# test1.net
KiCad netlist of a schematic drawn in Altium Designer
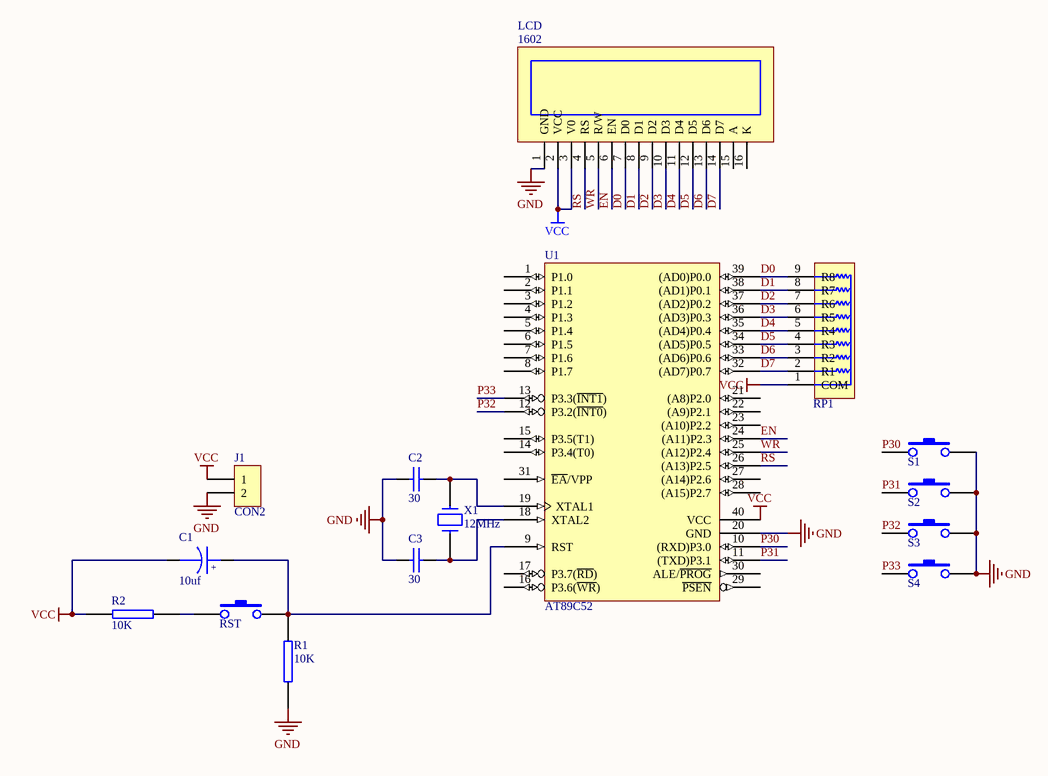
[diagram p0: test1.SchDoc]

(export (version "E")
  (design (tool "Eeschema 10.0.6"))
  (components
    (comp (ref "C1")
      (value "10uf")
      (footprint "C_SMT-5*5")
      (description "Capacitor")
      (libsource (lib "xinweidz") (part "电解电容"))
    )
    (comp (ref "C2")
      (value "30")
      (footprint "C0805")
      (description "Capacitor")
      (libsource (lib "*") (part "CAP"))
    )
    (comp (ref "C3")
      (value "30")
      (footprint "C0805")
      (description "Capacitor")
      (libsource (lib "*") (part "CAP"))
    )
    (comp (ref "J1")
      (value "CON2")
      (footprint "TC2")
      (description "Connector")
      (libsource (lib "51单片机最小系统.PcbDoc") (part "CON2"))
    )
    (comp (ref "LCD") (value "1602") (footprint "LCD1602") (libsource (lib "*") (part "LCM1602")))
    (comp (ref "R1") (value "10K") (footprint "C0805") (libsource (lib "*") (part "RES2")))
    (comp (ref "R2") (value "10K") (footprint "C0805") (libsource (lib "*") (part "RES2")))
    (comp (ref "RP1") (value "103") (footprint "R-9PIN") (libsource (lib "*") (part "RP8")))
    (comp (ref "RST")
      (value "SW-PB")
      (footprint "ANJIAN")
      (libsource (lib "51单片机最小系统.PcbDoc") (part "SW-PB"))
    )
    (comp (ref "S1") (value "SW-PB") (footprint "ANJIAN") (libsource (lib "51单片机最小系统.PcbDoc") (part "SW-PB")))
    (comp (ref "S2") (value "SW-PB") (footprint "ANJIAN") (libsource (lib "51单片机最小系统.PcbDoc") (part "SW-PB")))
    (comp (ref "S3") (value "SW-PB") (footprint "ANJIAN") (libsource (lib "51单片机最小系统.PcbDoc") (part "SW-PB")))
    (comp (ref "S4") (value "SW-PB") (footprint "ANJIAN") (libsource (lib "51单片机最小系统.PcbDoc") (part "SW-PB")))
    (comp (ref "U1")
      (value "AT89C52")
      (footprint "JINSUOZUO")
      (description "8-Bit Microcontroller with 4K Flash ROM")
      (libsource (lib "51单片机最小系统.PcbDoc") (part "AT89C51"))
    )
    (comp (ref "X1")
      (value "12MHz")
      (footprint "XTAL1")
      (description "Crystal")
      (libsource (lib "*") (part "CRYSTAL"))
    )
  )
  (nets
    (net (code "1") (name "/D0") (class "Default")
      (node (ref "LCD") (pin "7") (pinfunction "D0_7") (pintype "passive"))
      (node (ref "RP1") (pin "9") (pinfunction "R8_9") (pintype "passive"))
      (node (ref "U1") (pin "39") (pinfunction "(AD0)P0.0_39") (pintype "bidirectional"))
    )
    (net (code "2") (name "/D1") (class "Default")
      (node (ref "LCD") (pin "8") (pinfunction "D1_8") (pintype "passive"))
      (node (ref "RP1") (pin "8") (pinfunction "R7_8") (pintype "passive"))
      (node (ref "U1") (pin "38") (pinfunction "(AD1)P0.1_38") (pintype "bidirectional"))
    )
    (net (code "3") (name "/D2") (class "Default")
      (node (ref "LCD") (pin "9") (pinfunction "D2_9") (pintype "passive"))
      (node (ref "RP1") (pin "7") (pinfunction "R6_7") (pintype "passive"))
      (node (ref "U1") (pin "37") (pinfunction "(AD2)P0.2_37") (pintype "bidirectional"))
    )
    (net (code "4") (name "/D3") (class "Default")
      (node (ref "LCD") (pin "10") (pinfunction "D3_10") (pintype "passive"))
      (node (ref "RP1") (pin "6") (pinfunction "R5_6") (pintype "passive"))
      (node (ref "U1") (pin "36") (pinfunction "(AD3)P0.3_36") (pintype "bidirectional"))
    )
    (net (code "5") (name "/D4") (class "Default")
      (node (ref "LCD") (pin "11") (pinfunction "D4_11") (pintype "passive"))
      (node (ref "RP1") (pin "5") (pinfunction "R4_5") (pintype "passive"))
      (node (ref "U1") (pin "35") (pinfunction "(AD4)P0.4_35") (pintype "bidirectional"))
    )
    (net (code "6") (name "/D5") (class "Default")
      (node (ref "LCD") (pin "12") (pinfunction "D5_12") (pintype "passive"))
      (node (ref "RP1") (pin "4") (pinfunction "R3_4") (pintype "passive"))
      (node (ref "U1") (pin "34") (pinfunction "(AD5)P0.5_34") (pintype "bidirectional"))
    )
    (net (code "7") (name "/D6") (class "Default")
      (node (ref "LCD") (pin "13") (pinfunction "D6_13") (pintype "passive"))
      (node (ref "RP1") (pin "3") (pinfunction "R2_3") (pintype "passive"))
      (node (ref "U1") (pin "33") (pinfunction "(AD6)P0.6_33") (pintype "bidirectional"))
    )
    (net (code "8") (name "/D7") (class "Default")
      (node (ref "LCD") (pin "14") (pinfunction "D7_14") (pintype "passive"))
      (node (ref "RP1") (pin "2") (pinfunction "R1_2") (pintype "passive"))
      (node (ref "U1") (pin "32") (pinfunction "(AD7)P0.7_32") (pintype "bidirectional"))
    )
    (net (code "9") (name "/EN") (class "Default")
      (node (ref "LCD") (pin "6") (pinfunction "EN_6") (pintype "passive"))
      (node (ref "U1") (pin "24") (pinfunction "(A11)P2.3_24") (pintype "bidirectional"))
    )
    (net (code "10") (name "/P30") (class "Default")
      (node (ref "S1") (pin "1") (pinfunction "1_1") (pintype "passive"))
      (node (ref "U1") (pin "10") (pinfunction "(RXD)P3.0_10") (pintype "bidirectional"))
    )
    (net (code "11") (name "/P31") (class "Default")
      (node (ref "S2") (pin "1") (pinfunction "1_1") (pintype "passive"))
      (node (ref "U1") (pin "11") (pinfunction "(TXD)P3.1_11") (pintype "bidirectional"))
    )
    (net (code "12") (name "/P32") (class "Default")
      (node (ref "S3") (pin "1") (pinfunction "1_1") (pintype "passive"))
      (node (ref "U1") (pin "12") (pinfunction "P3.2(~{INT0})_12") (pintype "bidirectional"))
    )
    (net (code "13") (name "/P33") (class "Default")
      (node (ref "S4") (pin "1") (pinfunction "1_1") (pintype "passive"))
      (node (ref "U1") (pin "13") (pinfunction "P3.3(~{INT1})_13") (pintype "bidirectional"))
    )
    (net (code "14") (name "/RS") (class "Default")
      (node (ref "LCD") (pin "4") (pinfunction "RS_4") (pintype "passive"))
      (node (ref "U1") (pin "26") (pinfunction "(A13)P2.5_26") (pintype "bidirectional"))
    )
    (net (code "15") (name "/WR") (class "Default")
      (node (ref "LCD") (pin "5") (pinfunction "R/W_5") (pintype "passive"))
      (node (ref "U1") (pin "25") (pinfunction "(A12)P2.4_25") (pintype "bidirectional"))
    )
    (net (code "16") (name "GND") (class "Default")
      (node (ref "C2") (pin "2") (pinfunction "2_2") (pintype "passive"))
      (node (ref "C3") (pin "2") (pinfunction "2_2") (pintype "passive"))
      (node (ref "J1") (pin "2") (pinfunction "2_2") (pintype "passive"))
      (node (ref "LCD") (pin "1") (pinfunction "GND_1") (pintype "passive"))
      (node (ref "R1") (pin "2") (pinfunction "2_2") (pintype "passive"))
      (node (ref "S1") (pin "2") (pinfunction "2_2") (pintype "passive"))
      (node (ref "S2") (pin "2") (pinfunction "2_2") (pintype "passive"))
      (node (ref "S3") (pin "2") (pinfunction "2_2") (pintype "passive"))
      (node (ref "S4") (pin "2") (pinfunction "2_2") (pintype "passive"))
      (node (ref "U1") (pin "20") (pinfunction "GND_20") (pintype "power_in"))
    )
    (net (code "17") (name "Net-(R2-Pad2)") (class "Default")
      (node (ref "R2") (pin "2") (pinfunction "2_2") (pintype "passive"))
      (node (ref "RST") (pin "1") (pinfunction "1_1") (pintype "passive"))
    )
    (net (code "18") (name "Net-(U1-RST)") (class "Default")
      (node (ref "C1") (pin "2") (pinfunction "2_2") (pintype "passive"))
      (node (ref "R1") (pin "1") (pinfunction "1_1") (pintype "passive"))
      (node (ref "RST") (pin "2") (pinfunction "2_2") (pintype "passive"))
      (node (ref "U1") (pin "9") (pinfunction "RST_9") (pintype "input"))
    )
    (net (code "19") (name "Net-(U1-XTAL1)") (class "Default")
      (node (ref "C2") (pin "1") (pinfunction "1_1") (pintype "passive"))
      (node (ref "U1") (pin "19") (pinfunction "XTAL1_19") (pintype "input"))
      (node (ref "X1") (pin "1") (pinfunction "1_1") (pintype "passive"))
    )
    (net (code "20") (name "Net-(U1-XTAL2)") (class "Default")
      (node (ref "C3") (pin "1") (pinfunction "1_1") (pintype "passive"))
      (node (ref "U1") (pin "18") (pinfunction "XTAL2_18") (pintype "input"))
      (node (ref "X1") (pin "2") (pinfunction "2_2") (pintype "passive"))
    )
    (net (code "21") (name "VCC") (class "Default")
      (node (ref "C1") (pin "1") (pinfunction "1_1") (pintype "passive"))
      (node (ref "J1") (pin "1") (pinfunction "1_1") (pintype "passive"))
      (node (ref "LCD") (pin "2") (pinfunction "VCC_2") (pintype "passive"))
      (node (ref "LCD") (pin "3") (pinfunction "V0_3") (pintype "passive"))
      (node (ref "R2") (pin "1") (pinfunction "1_1") (pintype "passive"))
      (node (ref "RP1") (pin "1") (pinfunction "COM_1") (pintype "passive"))
      (node (ref "U1") (pin "40") (pinfunction "VCC_40") (pintype "power_in"))
    )
    (net (code "22") (name "unconnected-(LCD-A-Pad15)") (class "Default")
      (node (ref "LCD") (pin "15") (pinfunction "A_15") (pintype "passive"))
    )
    (net (code "23") (name "unconnected-(LCD-K-Pad16)") (class "Default")
      (node (ref "LCD") (pin "16") (pinfunction "K_16") (pintype "passive"))
    )
    (net (code "24") (name "unconnected-(U1-(A8)P2.0-Pad21)") (class "Default")
      (node (ref "U1") (pin "21") (pinfunction "(A8)P2.0_21") (pintype "bidirectional"))
    )
    (net (code "25") (name "unconnected-(U1-(A9)P2.1-Pad22)") (class "Default")
      (node (ref "U1") (pin "22") (pinfunction "(A9)P2.1_22") (pintype "bidirectional"))
    )
    (net (code "26") (name "unconnected-(U1-(A10)P2.2-Pad23)") (class "Default")
      (node (ref "U1") (pin "23") (pinfunction "(A10)P2.2_23") (pintype "bidirectional"))
    )
    (net (code "27") (name "unconnected-(U1-(A14)P2.6-Pad27)") (class "Default")
      (node (ref "U1") (pin "27") (pinfunction "(A14)P2.6_27") (pintype "bidirectional"))
    )
    (net (code "28") (name "unconnected-(U1-(A15)P2.7-Pad28)") (class "Default")
      (node (ref "U1") (pin "28") (pinfunction "(A15)P2.7_28") (pintype "bidirectional"))
    )
    (net (code "29") (name "unconnected-(U1-ALE{slash}~{PROG}-Pad30)") (class "Default")
      (node (ref "U1") (pin "30") (pinfunction "ALE/~{PROG}_30") (pintype "output"))
    )
    (net (code "30") (name "unconnected-(U1-P1.0-Pad1)") (class "Default")
      (node (ref "U1") (pin "1") (pinfunction "P1.0_1") (pintype "bidirectional"))
    )
    (net (code "31") (name "unconnected-(U1-P1.1-Pad2)") (class "Default")
      (node (ref "U1") (pin "2") (pinfunction "P1.1_2") (pintype "bidirectional"))
    )
    (net (code "32") (name "unconnected-(U1-P1.2-Pad3)") (class "Default")
      (node (ref "U1") (pin "3") (pinfunction "P1.2_3") (pintype "bidirectional"))
    )
    (net (code "33") (name "unconnected-(U1-P1.3-Pad4)") (class "Default")
      (node (ref "U1") (pin "4") (pinfunction "P1.3_4") (pintype "bidirectional"))
    )
    (net (code "34") (name "unconnected-(U1-P1.4-Pad5)") (class "Default")
      (node (ref "U1") (pin "5") (pinfunction "P1.4_5") (pintype "bidirectional"))
    )
    (net (code "35") (name "unconnected-(U1-P1.5-Pad6)") (class "Default")
      (node (ref "U1") (pin "6") (pinfunction "P1.5_6") (pintype "bidirectional"))
    )
    (net (code "36") (name "unconnected-(U1-P1.6-Pad7)") (class "Default")
      (node (ref "U1") (pin "7") (pinfunction "P1.6_7") (pintype "bidirectional"))
    )
    (net (code "37") (name "unconnected-(U1-P1.7-Pad8)") (class "Default")
      (node (ref "U1") (pin "8") (pinfunction "P1.7_8") (pintype "bidirectional"))
    )
    (net (code "38") (name "unconnected-(U1-P3.4(T0)-Pad14)") (class "Default")
      (node (ref "U1") (pin "14") (pinfunction "P3.4(T0)_14") (pintype "bidirectional"))
    )
    (net (code "39") (name "unconnected-(U1-P3.5(T1)-Pad15)") (class "Default")
      (node (ref "U1") (pin "15") (pinfunction "P3.5(T1)_15") (pintype "bidirectional"))
    )
    (net (code "40") (name "unconnected-(U1-P3.6(~{WR})-Pad16)") (class "Default")
      (node (ref "U1") (pin "16") (pinfunction "P3.6(~{WR})_16") (pintype "bidirectional"))
    )
    (net (code "41") (name "unconnected-(U1-P3.7(~{RD})-Pad17)") (class "Default")
      (node (ref "U1") (pin "17") (pinfunction "P3.7(~{RD})_17") (pintype "bidirectional"))
    )
    (net (code "42") (name "unconnected-(U1-~{EA}{slash}VPP-Pad31)") (class "Default")
      (node (ref "U1") (pin "31") (pinfunction "~{EA}/VPP_31") (pintype "input"))
    )
    (net (code "43") (name "unconnected-(U1-~{PSEN}-Pad29)") (class "Default")
      (node (ref "U1") (pin "29") (pinfunction "~{PSEN}_29") (pintype "output"))
    )
  )
)
